# DataFlash.net
KiCad netlist of a schematic drawn in EAGLE
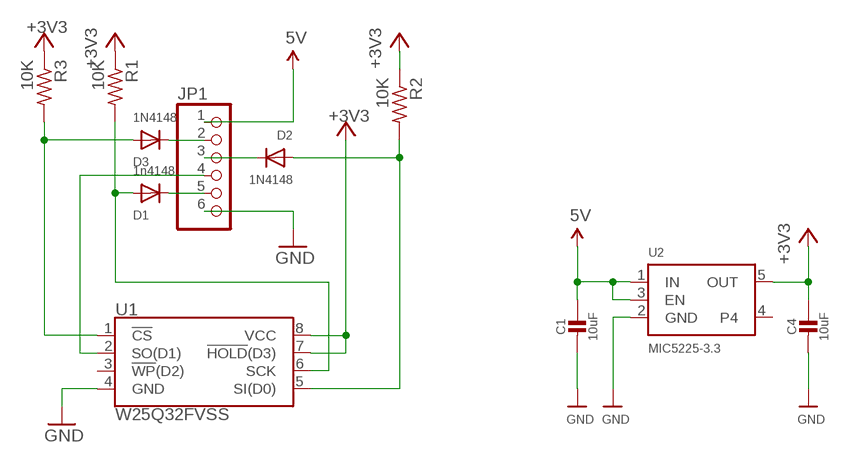
[diagram p0: schematic, sheet 1]

(export (version "E")
  (design (tool "Eeschema 10.0.6"))
  (components
    (comp (ref "C1")
      (value "10uF")
      (footprint "eagle-import:0805-NO")
      (libsource (lib "eagle-import") (part "CAP_CERAMIC0805-NOOUTLINE"))
    )
    (comp (ref "C4")
      (value "10uF")
      (footprint "eagle-import:0805-NO")
      (libsource (lib "eagle-import") (part "CAP_CERAMIC0805-NOOUTLINE"))
    )
    (comp (ref "D1")
      (value "1n4148")
      (footprint "eagle-import:SOD-323F")
      (libsource (lib "eagle-import") (part "DIODESOD-323F"))
    )
    (comp (ref "D2")
      (value "1N4148")
      (footprint "eagle-import:SOD-323F")
      (libsource (lib "eagle-import") (part "DIODESOD-323F"))
    )
    (comp (ref "D3")
      (value "1N4148")
      (footprint "eagle-import:SOD-323F")
      (libsource (lib "eagle-import") (part "DIODESOD-323F"))
    )
    (comp (ref "JP1")
      (value "HEADER-1X6ROUND")
      (footprint "eagle-import:1X06_ROUND")
      (libsource (lib "eagle-import") (part "HEADER-1X6ROUND"))
    )
    (comp (ref "R1")
      (value "10K")
      (footprint "eagle-import:R0805")
      (libsource (lib "eagle-import") (part "R-US_R0805"))
    )
    (comp (ref "R2")
      (value "10K")
      (footprint "eagle-import:R0805")
      (libsource (lib "eagle-import") (part "R-US_R0805"))
    )
    (comp (ref "R3")
      (value "10K")
      (footprint "eagle-import:R0805")
      (libsource (lib "eagle-import") (part "R-US_R0805"))
    )
    (comp (ref "U1")
      (value "W25Q32FVSS")
      (footprint "eagle-import:SOIC-8")
      (libsource (lib "eagle-import") (part "W25Q32FVSS"))
    )
    (comp (ref "U2")
      (value "MIC5225-3.3")
      (footprint "eagle-import:SOT23-5")
      (libsource (lib "eagle-import") (part "VREG_SOT23-5"))
    )
  )
  (nets
    (net (code "1") (name "+3V3") (class "Default")
      (node (ref "C4") (pin "1") (pinfunction "1_1") (pintype "passive"))
      (node (ref "R1") (pin "1") (pinfunction "1_1") (pintype "passive"))
      (node (ref "R2") (pin "1") (pinfunction "1_1") (pintype "passive"))
      (node (ref "R3") (pin "1") (pinfunction "1_1") (pintype "passive"))
      (node (ref "U1") (pin "7") (pinfunction "~{HOLD}(D3)_7") (pintype "bidirectional"))
      (node (ref "U1") (pin "8") (pinfunction "VCC_8") (pintype "bidirectional"))
      (node (ref "U2") (pin "5") (pinfunction "OUT_5") (pintype "power_in"))
    )
    (net (code "2") (name "5V") (class "Default")
      (node (ref "C1") (pin "1") (pinfunction "1_1") (pintype "passive"))
      (node (ref "JP1") (pin "1") (pinfunction "1_1") (pintype "passive"))
      (node (ref "U2") (pin "1") (pinfunction "IN_1") (pintype "power_in"))
      (node (ref "U2") (pin "3") (pinfunction "EN_3") (pintype "input"))
    )
    (net (code "3") (name "GND") (class "Default")
      (node (ref "C1") (pin "2") (pinfunction "2_2") (pintype "passive"))
      (node (ref "C4") (pin "2") (pinfunction "2_2") (pintype "passive"))
      (node (ref "JP1") (pin "6") (pinfunction "6_6") (pintype "passive"))
      (node (ref "U1") (pin "4") (pinfunction "GND_4") (pintype "bidirectional"))
      (node (ref "U2") (pin "2") (pinfunction "GND_2") (pintype "power_in"))
    )
    (net (code "4") (name "Net-(D1-PadC)") (class "Default")
      (node (ref "D1") (pin "C") (pinfunction "C_C") (pintype "passive"))
      (node (ref "JP1") (pin "5") (pinfunction "5_5") (pintype "passive"))
    )
    (net (code "5") (name "Net-(D2-PadC)") (class "Default")
      (node (ref "D2") (pin "C") (pinfunction "C_C") (pintype "passive"))
      (node (ref "JP1") (pin "3") (pinfunction "3_3") (pintype "passive"))
    )
    (net (code "6") (name "Net-(D3-PadC)") (class "Default")
      (node (ref "D3") (pin "C") (pinfunction "C_C") (pintype "passive"))
      (node (ref "JP1") (pin "2") (pinfunction "2_2") (pintype "passive"))
    )
    (net (code "7") (name "Net-(U1-SCK)") (class "Default")
      (node (ref "D1") (pin "A") (pinfunction "A_A") (pintype "passive"))
      (node (ref "R1") (pin "2") (pinfunction "2_2") (pintype "passive"))
      (node (ref "U1") (pin "6") (pinfunction "SCK_6") (pintype "bidirectional"))
    )
    (net (code "8") (name "Net-(U1-SI(D0))") (class "Default")
      (node (ref "D2") (pin "A") (pinfunction "A_A") (pintype "passive"))
      (node (ref "R2") (pin "2") (pinfunction "2_2") (pintype "passive"))
      (node (ref "U1") (pin "5") (pinfunction "SI(D0)_5") (pintype "bidirectional"))
    )
    (net (code "9") (name "Net-(U1-SO(D1))") (class "Default")
      (node (ref "JP1") (pin "4") (pinfunction "4_4") (pintype "passive"))
      (node (ref "U1") (pin "2") (pinfunction "SO(D1)_2") (pintype "bidirectional"))
    )
    (net (code "10") (name "Net-(U1-~{CS})") (class "Default")
      (node (ref "D3") (pin "A") (pinfunction "A_A") (pintype "passive"))
      (node (ref "R3") (pin "2") (pinfunction "2_2") (pintype "passive"))
      (node (ref "U1") (pin "1") (pinfunction "~{CS}_1") (pintype "bidirectional"))
    )
    (net (code "11") (name "unconnected-(U1-~{WP}(D2)-Pad3)") (class "Default")
      (node (ref "U1") (pin "3") (pinfunction "~{WP}(D2)_3") (pintype "bidirectional"))
    )
    (net (code "12") (name "unconnected-(U2-P4-Pad4)") (class "Default")
      (node (ref "U2") (pin "4") (pinfunction "P4_4") (pintype "bidirectional"))
    )
  )
)
